# gateDriverProto.net
KiCad netlist of a schematic drawn in EAGLE
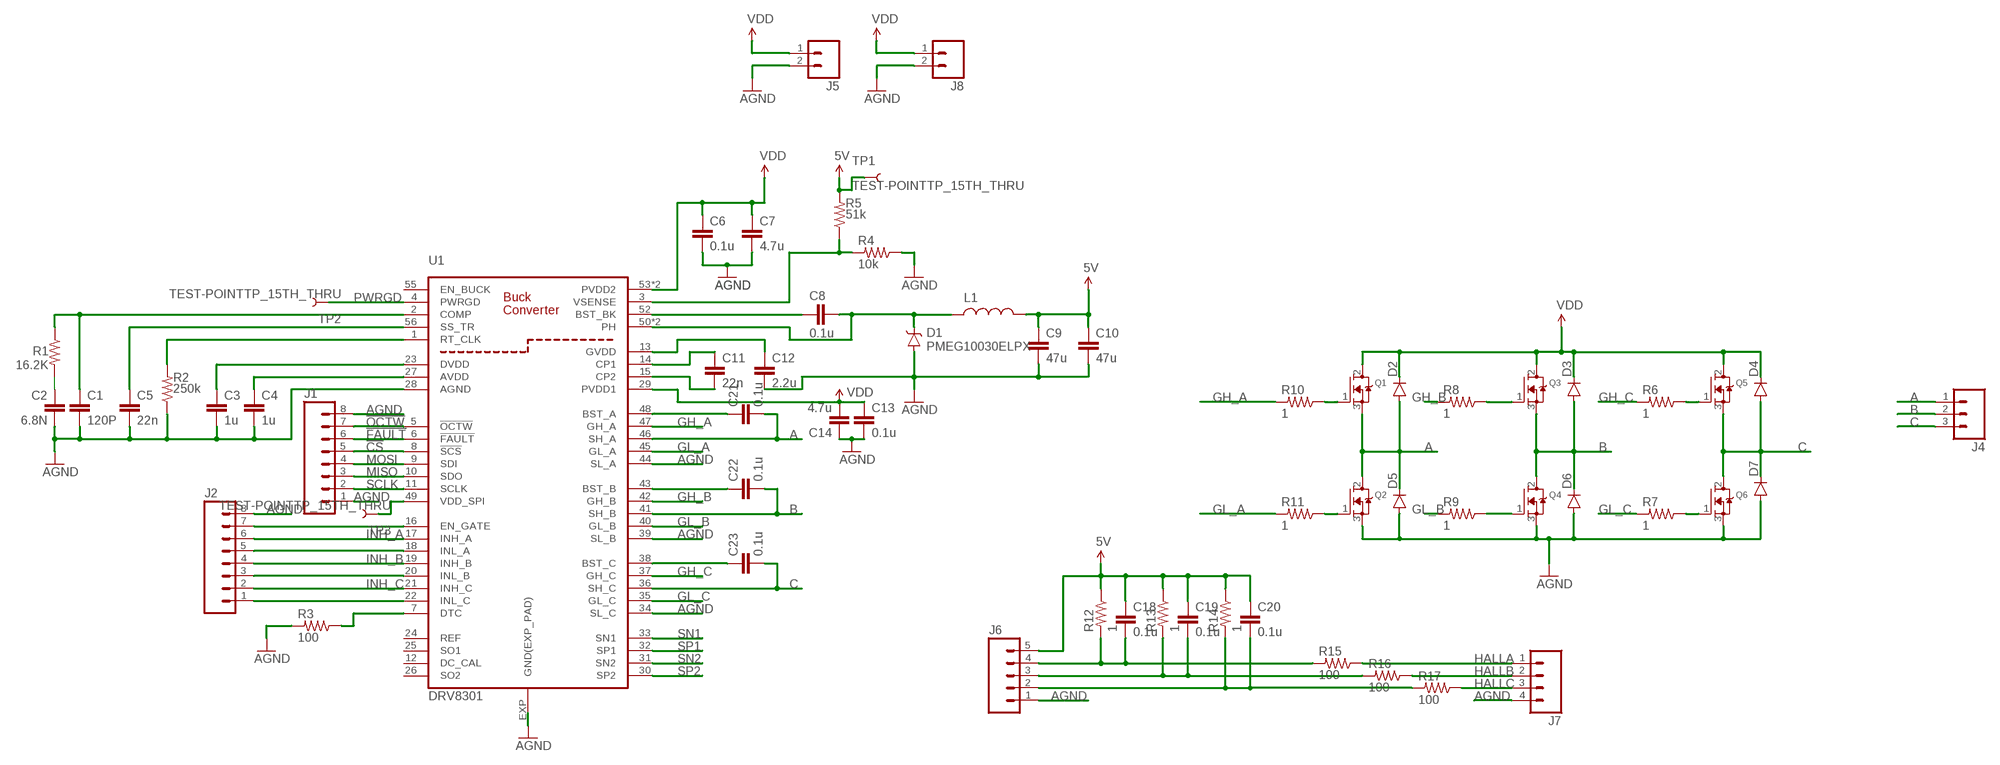
[diagram p0: schematic, sheet 1]

(export (version "E")
  (design (tool "Eeschema 10.0.6"))
  (components
    (comp (ref "C1")
      (value "120P")
      (footprint "eagle-import:0805")
      (libsource (lib "eagle-import") (part "CAP0805"))
    )
    (comp (ref "C2")
      (value "6.8N")
      (footprint "eagle-import:0805")
      (libsource (lib "eagle-import") (part "CAP0805"))
    )
    (comp (ref "C3")
      (value "1u")
      (footprint "eagle-import:0805")
      (libsource (lib "eagle-import") (part "CAP0805"))
    )
    (comp (ref "C4")
      (value "1u")
      (footprint "eagle-import:0805")
      (libsource (lib "eagle-import") (part "CAP0805"))
    )
    (comp (ref "C5")
      (value "22n")
      (footprint "eagle-import:0805")
      (libsource (lib "eagle-import") (part "CAP0805"))
    )
    (comp (ref "C6")
      (value "0.1u")
      (footprint "eagle-import:0805")
      (libsource (lib "eagle-import") (part "CAP0805"))
    )
    (comp (ref "C7")
      (value "4.7u")
      (footprint "eagle-import:1210")
      (libsource (lib "eagle-import") (part "CAP1210"))
    )
    (comp (ref "C8")
      (value "0.1u")
      (footprint "eagle-import:0805")
      (libsource (lib "eagle-import") (part "CAP0805"))
    )
    (comp (ref "C9")
      (value "47u")
      (footprint "eagle-import:1210")
      (libsource (lib "eagle-import") (part "CAP1210"))
    )
    (comp (ref "C10")
      (value "47u")
      (footprint "eagle-import:1210")
      (libsource (lib "eagle-import") (part "CAP1210"))
    )
    (comp (ref "C11")
      (value "22n")
      (footprint "eagle-import:0805")
      (libsource (lib "eagle-import") (part "CAP0805"))
    )
    (comp (ref "C12")
      (value "2.2u")
      (footprint "eagle-import:1210")
      (libsource (lib "eagle-import") (part "CAP1210"))
    )
    (comp (ref "C13")
      (value "0.1u")
      (footprint "eagle-import:0805")
      (libsource (lib "eagle-import") (part "CAP0805"))
    )
    (comp (ref "C14")
      (value "4.7u")
      (footprint "eagle-import:1210")
      (libsource (lib "eagle-import") (part "CAP1210"))
    )
    (comp (ref "C18")
      (value "0.1u")
      (footprint "eagle-import:0805")
      (libsource (lib "eagle-import") (part "CAP0805"))
    )
    (comp (ref "C19")
      (value "0.1u")
      (footprint "eagle-import:0805")
      (libsource (lib "eagle-import") (part "CAP0805"))
    )
    (comp (ref "C20")
      (value "0.1u")
      (footprint "eagle-import:0805")
      (libsource (lib "eagle-import") (part "CAP0805"))
    )
    (comp (ref "C21")
      (value "0.1u")
      (footprint "eagle-import:CAP-PTH-SMALL")
      (libsource (lib "eagle-import") (part "SparkFun-Passives_CAPPTH"))
    )
    (comp (ref "C22")
      (value "0.1u")
      (footprint "eagle-import:CAP-PTH-SMALL")
      (libsource (lib "eagle-import") (part "SparkFun-Passives_CAPPTH"))
    )
    (comp (ref "C23")
      (value "0.1u")
      (footprint "eagle-import:CAP-PTH-SMALL")
      (libsource (lib "eagle-import") (part "SparkFun-Passives_CAPPTH"))
    )
    (comp (ref "D1")
      (value "PMEG10030ELPX")
      (footprint "eagle-import:SMB-DIODE")
      (libsource (lib "eagle-import") (part "PMEG10030ELPX"))
    )
    (comp (ref "D2")
      (value "DIODEPTH")
      (footprint "eagle-import:DIODE-1N4001")
      (libsource (lib "eagle-import") (part "DIODEPTH"))
    )
    (comp (ref "D3")
      (value "DIODEPTH")
      (footprint "eagle-import:DIODE-1N4001")
      (libsource (lib "eagle-import") (part "DIODEPTH"))
    )
    (comp (ref "D4")
      (value "DIODEPTH")
      (footprint "eagle-import:DIODE-1N4001")
      (libsource (lib "eagle-import") (part "DIODEPTH"))
    )
    (comp (ref "D5")
      (value "DIODEPTH")
      (footprint "eagle-import:DIODE-1N4001")
      (libsource (lib "eagle-import") (part "DIODEPTH"))
    )
    (comp (ref "D6")
      (value "DIODEPTH")
      (footprint "eagle-import:DIODE-1N4001")
      (libsource (lib "eagle-import") (part "DIODEPTH"))
    )
    (comp (ref "D7")
      (value "DIODEPTH")
      (footprint "eagle-import:DIODE-1N4001")
      (libsource (lib "eagle-import") (part "DIODEPTH"))
    )
    (comp (ref "J1")
      (value "M08")
      (footprint "eagle-import:1X08_ROUND")
      (libsource (lib "eagle-import") (part "M08"))
    )
    (comp (ref "J2")
      (value "M08")
      (footprint "eagle-import:1X08_ROUND")
      (libsource (lib "eagle-import") (part "M08"))
    )
    (comp (ref "J4")
      (value "M03LONGPADS")
      (footprint "eagle-import:1X03_LONGPADS")
      (libsource (lib "eagle-import") (part "M03LONGPADS"))
    )
    (comp (ref "J5")
      (value "M02LOCK_LONGPADS")
      (footprint "eagle-import:1X02_LOCK_LONGPADS")
      (libsource (lib "eagle-import") (part "M02LOCK_LONGPADS"))
    )
    (comp (ref "J6")
      (value "M05PTH_LONGPADS")
      (footprint "eagle-import:1X05_LONGPADS")
      (libsource (lib "eagle-import") (part "M05PTH_LONGPADS"))
    )
    (comp (ref "J7")
      (value "M04PTH")
      (footprint "eagle-import:1X04")
      (libsource (lib "eagle-import") (part "M04PTH"))
    )
    (comp (ref "J8")
      (value "M02LOCK_LONGPADS")
      (footprint "eagle-import:1X02_LOCK_LONGPADS")
      (libsource (lib "eagle-import") (part "M02LOCK_LONGPADS"))
    )
    (comp (ref "L1")
      (value "INDUCTORPWR")
      (footprint "eagle-import:CDRH125")
      (libsource (lib "eagle-import") (part "INDUCTORPWR"))
    )
    (comp (ref "Q1")
      (value "MOSFET-NGDS_TO220V")
      (footprint "eagle-import:TO220V")
      (libsource (lib "eagle-import") (part "MOSFET-NGDS_TO220V"))
    )
    (comp (ref "Q2")
      (value "MOSFET-NGDS_TO220V")
      (footprint "eagle-import:TO220V")
      (libsource (lib "eagle-import") (part "MOSFET-NGDS_TO220V"))
    )
    (comp (ref "Q3")
      (value "MOSFET-NGDS_TO220V")
      (footprint "eagle-import:TO220V")
      (libsource (lib "eagle-import") (part "MOSFET-NGDS_TO220V"))
    )
    (comp (ref "Q4")
      (value "MOSFET-NGDS_TO220V")
      (footprint "eagle-import:TO220V")
      (libsource (lib "eagle-import") (part "MOSFET-NGDS_TO220V"))
    )
    (comp (ref "Q5")
      (value "MOSFET-NGDS_TO220V")
      (footprint "eagle-import:TO220V")
      (libsource (lib "eagle-import") (part "MOSFET-NGDS_TO220V"))
    )
    (comp (ref "Q6")
      (value "MOSFET-NGDS_TO220V")
      (footprint "eagle-import:TO220V")
      (libsource (lib "eagle-import") (part "MOSFET-NGDS_TO220V"))
    )
    (comp (ref "R1")
      (value "16.2K")
      (footprint "eagle-import:AXIAL-0.1")
      (libsource (lib "eagle-import") (part "RESISTORPTH-1/4W-VERT"))
    )
    (comp (ref "R2")
      (value "250k")
      (footprint "eagle-import:AXIAL-0.1")
      (libsource (lib "eagle-import") (part "RESISTORPTH-1/4W-VERT"))
    )
    (comp (ref "R3")
      (value "100")
      (footprint "eagle-import:AXIAL-0.1")
      (libsource (lib "eagle-import") (part "RESISTORPTH-1/4W-VERT"))
    )
    (comp (ref "R4")
      (value "10k")
      (footprint "eagle-import:AXIAL-0.1")
      (libsource (lib "eagle-import") (part "RESISTORPTH-1/4W-VERT"))
    )
    (comp (ref "R5")
      (value "51k")
      (footprint "eagle-import:AXIAL-0.1")
      (libsource (lib "eagle-import") (part "RESISTORPTH-1/4W-VERT"))
    )
    (comp (ref "R6")
      (value "1")
      (footprint "eagle-import:AXIAL-0.1")
      (libsource (lib "eagle-import") (part "RESISTORPTH-1/4W-VERT"))
    )
    (comp (ref "R7")
      (value "1")
      (footprint "eagle-import:AXIAL-0.1")
      (libsource (lib "eagle-import") (part "RESISTORPTH-1/4W-VERT"))
    )
    (comp (ref "R8")
      (value "1")
      (footprint "eagle-import:AXIAL-0.1")
      (libsource (lib "eagle-import") (part "RESISTORPTH-1/4W-VERT"))
    )
    (comp (ref "R9")
      (value "1")
      (footprint "eagle-import:AXIAL-0.1")
      (libsource (lib "eagle-import") (part "RESISTORPTH-1/4W-VERT"))
    )
    (comp (ref "R10")
      (value "1")
      (footprint "eagle-import:AXIAL-0.1")
      (libsource (lib "eagle-import") (part "RESISTORPTH-1/4W-VERT"))
    )
    (comp (ref "R11")
      (value "1")
      (footprint "eagle-import:AXIAL-0.1")
      (libsource (lib "eagle-import") (part "RESISTORPTH-1/4W-VERT"))
    )
    (comp (ref "R12")
      (value "1")
      (footprint "eagle-import:AXIAL-0.1")
      (libsource (lib "eagle-import") (part "RESISTORPTH-1/4W-VERT"))
    )
    (comp (ref "R13")
      (value "1")
      (footprint "eagle-import:AXIAL-0.1")
      (libsource (lib "eagle-import") (part "RESISTORPTH-1/4W-VERT"))
    )
    (comp (ref "R14")
      (value "1")
      (footprint "eagle-import:AXIAL-0.1")
      (libsource (lib "eagle-import") (part "RESISTORPTH-1/4W-VERT"))
    )
    (comp (ref "R15")
      (value "100")
      (footprint "eagle-import:AXIAL-0.1")
      (libsource (lib "eagle-import") (part "RESISTORPTH-1/4W-VERT"))
    )
    (comp (ref "R16")
      (value "100")
      (footprint "eagle-import:AXIAL-0.1")
      (libsource (lib "eagle-import") (part "RESISTORPTH-1/4W-VERT"))
    )
    (comp (ref "R17")
      (value "100")
      (footprint "eagle-import:AXIAL-0.1")
      (libsource (lib "eagle-import") (part "RESISTORPTH-1/4W-VERT"))
    )
    (comp (ref "TP1")
      (value "TEST-POINTTP_15TH_THRU")
      (footprint "eagle-import:TP_15TH")
      (libsource (lib "eagle-import") (part "TEST-POINTTP_15TH_THRU"))
    )
    (comp (ref "TP2")
      (value "TEST-POINTTP_15TH_THRU")
      (footprint "eagle-import:TP_15TH")
      (libsource (lib "eagle-import") (part "TEST-POINTTP_15TH_THRU"))
    )
    (comp (ref "TP3")
      (value "TEST-POINTTP_15TH_THRU")
      (footprint "eagle-import:TP_15TH")
      (libsource (lib "eagle-import") (part "TEST-POINTTP_15TH_THRU"))
    )
    (comp (ref "U1")
      (value "DRV8301")
      (footprint "eagle-import:HTSSOP_56")
      (libsource (lib "eagle-import") (part "DRV8301"))
    )
  )
  (nets
    (net (code "1") (name "/A") (class "Default")
      (node (ref "C21") (pin "2") (pinfunction "2_2") (pintype "passive"))
      (node (ref "D2") (pin "A") (pinfunction "A_A") (pintype "passive"))
      (node (ref "D5") (pin "C") (pinfunction "C_C") (pintype "passive"))
      (node (ref "J4") (pin "1") (pinfunction "1_1") (pintype "passive"))
      (node (ref "Q1") (pin "3") (pinfunction "S_3") (pintype "bidirectional"))
      (node (ref "Q2") (pin "2") (pinfunction "D_2") (pintype "bidirectional"))
      (node (ref "U1") (pin "46") (pinfunction "SH_A_46") (pintype "input"))
    )
    (net (code "2") (name "/B") (class "Default")
      (node (ref "C22") (pin "2") (pinfunction "2_2") (pintype "passive"))
      (node (ref "D3") (pin "A") (pinfunction "A_A") (pintype "passive"))
      (node (ref "D6") (pin "C") (pinfunction "C_C") (pintype "passive"))
      (node (ref "J4") (pin "2") (pinfunction "2_2") (pintype "passive"))
      (node (ref "Q3") (pin "3") (pinfunction "S_3") (pintype "bidirectional"))
      (node (ref "Q4") (pin "2") (pinfunction "D_2") (pintype "bidirectional"))
      (node (ref "U1") (pin "41") (pinfunction "SH_B_41") (pintype "input"))
    )
    (net (code "3") (name "/C") (class "Default")
      (node (ref "C23") (pin "2") (pinfunction "2_2") (pintype "passive"))
      (node (ref "D4") (pin "A") (pinfunction "A_A") (pintype "passive"))
      (node (ref "D7") (pin "C") (pinfunction "C_C") (pintype "passive"))
      (node (ref "J4") (pin "3") (pinfunction "3_3") (pintype "passive"))
      (node (ref "Q5") (pin "3") (pinfunction "S_3") (pintype "bidirectional"))
      (node (ref "Q6") (pin "2") (pinfunction "D_2") (pintype "bidirectional"))
      (node (ref "U1") (pin "36") (pinfunction "SH_C_36") (pintype "input"))
    )
    (net (code "4") (name "/GH_A") (class "Default")
      (node (ref "R10") (pin "P$2") (pinfunction "2_P$2") (pintype "passive"))
      (node (ref "U1") (pin "47") (pinfunction "GH_A_47") (pintype "output"))
    )
    (net (code "5") (name "/GH_B") (class "Default")
      (node (ref "R8") (pin "P$2") (pinfunction "2_P$2") (pintype "passive"))
      (node (ref "U1") (pin "42") (pinfunction "GH_B_42") (pintype "output"))
    )
    (net (code "6") (name "/GH_C") (class "Default")
      (node (ref "R6") (pin "P$2") (pinfunction "2_P$2") (pintype "passive"))
      (node (ref "U1") (pin "37") (pinfunction "GH_C_37") (pintype "output"))
    )
    (net (code "7") (name "/GL_A") (class "Default")
      (node (ref "R11") (pin "P$2") (pinfunction "2_P$2") (pintype "passive"))
      (node (ref "U1") (pin "45") (pinfunction "GL_A_45") (pintype "output"))
    )
    (net (code "8") (name "/GL_B") (class "Default")
      (node (ref "R9") (pin "P$2") (pinfunction "2_P$2") (pintype "passive"))
      (node (ref "U1") (pin "40") (pinfunction "GL_B_40") (pintype "output"))
    )
    (net (code "9") (name "/GL_C") (class "Default")
      (node (ref "R7") (pin "P$2") (pinfunction "2_P$2") (pintype "passive"))
      (node (ref "U1") (pin "35") (pinfunction "GL_C_35") (pintype "output"))
    )
    (net (code "10") (name "/HALLA") (class "Default")
      (node (ref "J7") (pin "1") (pinfunction "1_1") (pintype "passive"))
      (node (ref "R15") (pin "P$1") (pinfunction "1_P$1") (pintype "passive"))
    )
    (net (code "11") (name "/HALLB") (class "Default")
      (node (ref "J7") (pin "2") (pinfunction "2_2") (pintype "passive"))
      (node (ref "R16") (pin "P$1") (pinfunction "1_P$1") (pintype "passive"))
    )
    (net (code "12") (name "/HALLC") (class "Default")
      (node (ref "J7") (pin "3") (pinfunction "3_3") (pintype "passive"))
      (node (ref "R17") (pin "P$1") (pinfunction "1_P$1") (pintype "passive"))
    )
    (net (code "13") (name "/INH_A") (class "Default")
      (node (ref "J2") (pin "6") (pinfunction "6_6") (pintype "passive"))
      (node (ref "U1") (pin "17") (pinfunction "INH_A_17") (pintype "input"))
    )
    (net (code "14") (name "/INH_B") (class "Default")
      (node (ref "J2") (pin "4") (pinfunction "4_4") (pintype "passive"))
      (node (ref "U1") (pin "19") (pinfunction "INH_B_19") (pintype "input"))
    )
    (net (code "15") (name "/INH_C") (class "Default")
      (node (ref "J2") (pin "2") (pinfunction "2_2") (pintype "passive"))
      (node (ref "U1") (pin "21") (pinfunction "INH_C_21") (pintype "input"))
    )
    (net (code "16") (name "/MISO") (class "Default")
      (node (ref "J1") (pin "3") (pinfunction "3_3") (pintype "passive"))
      (node (ref "U1") (pin "10") (pinfunction "SDO_10") (pintype "output"))
    )
    (net (code "17") (name "/MOSI") (class "Default")
      (node (ref "J1") (pin "4") (pinfunction "4_4") (pintype "passive"))
      (node (ref "U1") (pin "9") (pinfunction "SDI_9") (pintype "input"))
    )
    (net (code "18") (name "/PWRGD") (class "Default")
      (node (ref "TP2") (pin "P$1") (pinfunction "1_P$1") (pintype "bidirectional"))
      (node (ref "U1") (pin "4") (pinfunction "PWRGD_4") (pintype "output"))
    )
    (net (code "19") (name "/SCLK") (class "Default")
      (node (ref "J1") (pin "2") (pinfunction "2_2") (pintype "passive"))
      (node (ref "U1") (pin "11") (pinfunction "SCLK_11") (pintype "input"))
    )
    (net (code "20") (name "/SN1") (class "Default")
      (node (ref "U1") (pin "33") (pinfunction "SN1_33") (pintype "input"))
    )
    (net (code "21") (name "/SN2") (class "Default")
      (node (ref "U1") (pin "31") (pinfunction "SN2_31") (pintype "input"))
    )
    (net (code "22") (name "/SP1") (class "Default")
      (node (ref "U1") (pin "32") (pinfunction "SP1_32") (pintype "input"))
    )
    (net (code "23") (name "/SP2") (class "Default")
      (node (ref "U1") (pin "30") (pinfunction "SP2_30") (pintype "input"))
    )
    (net (code "24") (name "/~{CS}") (class "Default")
      (node (ref "J1") (pin "5") (pinfunction "5_5") (pintype "passive"))
      (node (ref "U1") (pin "8") (pinfunction "~{SCS}_8") (pintype "input"))
    )
    (net (code "25") (name "/~{FAULT}") (class "Default")
      (node (ref "J1") (pin "6") (pinfunction "6_6") (pintype "passive"))
      (node (ref "U1") (pin "6") (pinfunction "~{FAULT}_6") (pintype "output"))
    )
    (net (code "26") (name "/~{OCTW}") (class "Default")
      (node (ref "J1") (pin "7") (pinfunction "7_7") (pintype "passive"))
      (node (ref "U1") (pin "5") (pinfunction "~{OCTW}_5") (pintype "output"))
    )
    (net (code "27") (name "5V") (class "Default")
      (node (ref "C10") (pin "1") (pinfunction "1_1") (pintype "passive"))
      (node (ref "C18") (pin "1") (pinfunction "1_1") (pintype "passive"))
      (node (ref "C19") (pin "1") (pinfunction "1_1") (pintype "passive"))
      (node (ref "C20") (pin "1") (pinfunction "1_1") (pintype "passive"))
      (node (ref "C9") (pin "1") (pinfunction "1_1") (pintype "passive"))
      (node (ref "J6") (pin "5") (pinfunction "5_5") (pintype "passive"))
      (node (ref "L1") (pin "2") (pinfunction "2_2") (pintype "passive"))
      (node (ref "R12") (pin "P$1") (pinfunction "1_P$1") (pintype "passive"))
      (node (ref "R13") (pin "P$1") (pinfunction "1_P$1") (pintype "passive"))
      (node (ref "R14") (pin "P$1") (pinfunction "1_P$1") (pintype "passive"))
      (node (ref "R5") (pin "P$2") (pinfunction "2_P$2") (pintype "passive"))
      (node (ref "TP1") (pin "P$1") (pinfunction "1_P$1") (pintype "bidirectional"))
    )
    (net (code "28") (name "AGND") (class "Default")
      (node (ref "C1") (pin "2") (pinfunction "2_2") (pintype "passive"))
      (node (ref "C10") (pin "2") (pinfunction "2_2") (pintype "passive"))
      (node (ref "C12") (pin "2") (pinfunction "2_2") (pintype "passive"))
      (node (ref "C13") (pin "2") (pinfunction "2_2") (pintype "passive"))
      (node (ref "C14") (pin "1") (pinfunction "1_1") (pintype "passive"))
      (node (ref "C2") (pin "2") (pinfunction "2_2") (pintype "passive"))
      (node (ref "C3") (pin "2") (pinfunction "2_2") (pintype "passive"))
      (node (ref "C4") (pin "2") (pinfunction "2_2") (pintype "passive"))
      (node (ref "C5") (pin "2") (pinfunction "2_2") (pintype "passive"))
      (node (ref "C6") (pin "2") (pinfunction "2_2") (pintype "passive"))
      (node (ref "C7") (pin "2") (pinfunction "2_2") (pintype "passive"))
      (node (ref "C9") (pin "2") (pinfunction "2_2") (pintype "passive"))
      (node (ref "D1") (pin "A") (pinfunction "A_A") (pintype "passive"))
      (node (ref "D5") (pin "A") (pinfunction "A_A") (pintype "passive"))
      (node (ref "D6") (pin "A") (pinfunction "A_A") (pintype "passive"))
      (node (ref "D7") (pin "A") (pinfunction "A_A") (pintype "passive"))
      (node (ref "J1") (pin "1") (pinfunction "1_1") (pintype "passive"))
      (node (ref "J1") (pin "8") (pinfunction "8_8") (pintype "passive"))
      (node (ref "J2") (pin "8") (pinfunction "8_8") (pintype "passive"))
      (node (ref "J5") (pin "2") (pinfunction "2_2") (pintype "passive"))
      (node (ref "J6") (pin "1") (pinfunction "1_1") (pintype "passive"))
      (node (ref "J7") (pin "4") (pinfunction "4_4") (pintype "passive"))
      (node (ref "J8") (pin "2") (pinfunction "2_2") (pintype "passive"))
      (node (ref "Q2") (pin "3") (pinfunction "S_3") (pintype "bidirectional"))
      (node (ref "Q4") (pin "3") (pinfunction "S_3") (pintype "bidirectional"))
      (node (ref "Q6") (pin "3") (pinfunction "S_3") (pintype "bidirectional"))
      (node (ref "R2") (pin "P$1") (pinfunction "1_P$1") (pintype "passive"))
      (node (ref "R3") (pin "P$2") (pinfunction "2_P$2") (pintype "passive"))
      (node (ref "R4") (pin "P$1") (pinfunction "1_P$1") (pintype "passive"))
      (node (ref "U1") (pin "28") (pinfunction "AGND_28") (pintype "power_in"))
      (node (ref "U1") (pin "34") (pinfunction "SL_C_34") (pintype "input"))
      (node (ref "U1") (pin "39") (pinfunction "SL_B_39") (pintype "input"))
      (node (ref "U1") (pin "44") (pinfunction "SL_A_44") (pintype "input"))
      (node (ref "U1") (pin "EXP") (pinfunction "GND(EXP_PAD)_EXP") (pintype "bidirectional"))
    )
    (net (code "29") (name "Net-(C8-Pad2)") (class "Default")
      (node (ref "C8") (pin "2") (pinfunction "2_2") (pintype "passive"))
      (node (ref "D1") (pin "C") (pinfunction "C_C") (pintype "passive"))
      (node (ref "L1") (pin "1") (pinfunction "1_1") (pintype "passive"))
      (node (ref "U1") (pin "50") (pinfunction "PH_50") (pintype "output"))
      (node (ref "U1") (pin "51") (pinfunction "PH_51") (pintype "output"))
    )
    (net (code "30") (name "Net-(Q1-G)") (class "Default")
      (node (ref "Q1") (pin "1") (pinfunction "G_1") (pintype "bidirectional"))
      (node (ref "R10") (pin "P$1") (pinfunction "1_P$1") (pintype "passive"))
    )
    (net (code "31") (name "Net-(Q2-G)") (class "Default")
      (node (ref "Q2") (pin "1") (pinfunction "G_1") (pintype "bidirectional"))
      (node (ref "R11") (pin "P$1") (pinfunction "1_P$1") (pintype "passive"))
    )
    (net (code "32") (name "Net-(Q3-G)") (class "Default")
      (node (ref "Q3") (pin "1") (pinfunction "G_1") (pintype "bidirectional"))
      (node (ref "R8") (pin "P$1") (pinfunction "1_P$1") (pintype "passive"))
    )
    (net (code "33") (name "Net-(Q4-G)") (class "Default")
      (node (ref "Q4") (pin "1") (pinfunction "G_1") (pintype "bidirectional"))
      (node (ref "R9") (pin "P$1") (pinfunction "1_P$1") (pintype "passive"))
    )
    (net (code "34") (name "Net-(Q5-G)") (class "Default")
      (node (ref "Q5") (pin "1") (pinfunction "G_1") (pintype "bidirectional"))
      (node (ref "R6") (pin "P$1") (pinfunction "1_P$1") (pintype "passive"))
    )
    (net (code "35") (name "Net-(Q6-G)") (class "Default")
      (node (ref "Q6") (pin "1") (pinfunction "G_1") (pintype "bidirectional"))
      (node (ref "R7") (pin "P$1") (pinfunction "1_P$1") (pintype "passive"))
    )
    (net (code "36") (name "Net-(R1-1)") (class "Default")
      (node (ref "C1") (pin "1") (pinfunction "1_1") (pintype "passive"))
      (node (ref "R1") (pin "P$1") (pinfunction "1_P$1") (pintype "passive"))
      (node (ref "U1") (pin "2") (pinfunction "COMP_2") (pintype "output"))
    )
    (net (code "37") (name "Net-(R1-2)") (class "Default")
      (node (ref "C2") (pin "1") (pinfunction "1_1") (pintype "passive"))
      (node (ref "R1") (pin "P$2") (pinfunction "2_P$2") (pintype "passive"))
    )
    (net (code "38") (name "Net-(R2-2)") (class "Default")
      (node (ref "R2") (pin "P$2") (pinfunction "2_P$2") (pintype "passive"))
      (node (ref "U1") (pin "1") (pinfunction "RT_CLK_1") (pintype "input"))
    )
    (net (code "39") (name "Net-(R3-1)") (class "Default")
      (node (ref "R3") (pin "P$1") (pinfunction "1_P$1") (pintype "passive"))
      (node (ref "U1") (pin "7") (pinfunction "DTC_7") (pintype "input"))
    )
    (net (code "40") (name "Net-(R4-2)") (class "Default")
      (node (ref "R4") (pin "P$2") (pinfunction "2_P$2") (pintype "passive"))
      (node (ref "R5") (pin "P$1") (pinfunction "1_P$1") (pintype "passive"))
      (node (ref "U1") (pin "3") (pinfunction "VSENSE_3") (pintype "input"))
    )
    (net (code "41") (name "Net-(R12-2)") (class "Default")
      (node (ref "C18") (pin "2") (pinfunction "2_2") (pintype "passive"))
      (node (ref "J6") (pin "4") (pinfunction "4_4") (pintype "passive"))
      (node (ref "R12") (pin "P$2") (pinfunction "2_P$2") (pintype "passive"))
      (node (ref "R15") (pin "P$2") (pinfunction "2_P$2") (pintype "passive"))
    )
    (net (code "42") (name "Net-(R13-2)") (class "Default")
      (node (ref "C19") (pin "2") (pinfunction "2_2") (pintype "passive"))
      (node (ref "J6") (pin "3") (pinfunction "3_3") (pintype "passive"))
      (node (ref "R13") (pin "P$2") (pinfunction "2_P$2") (pintype "passive"))
      (node (ref "R16") (pin "P$2") (pinfunction "2_P$2") (pintype "passive"))
    )
    (net (code "43") (name "Net-(R14-2)") (class "Default")
      (node (ref "C20") (pin "2") (pinfunction "2_2") (pintype "passive"))
      (node (ref "J6") (pin "2") (pinfunction "2_2") (pintype "passive"))
      (node (ref "R14") (pin "P$2") (pinfunction "2_P$2") (pintype "passive"))
      (node (ref "R17") (pin "P$2") (pinfunction "2_P$2") (pintype "passive"))
    )
    (net (code "44") (name "Net-(TP3-1)") (class "Default")
      (node (ref "TP3") (pin "P$1") (pinfunction "1_P$1") (pintype "bidirectional"))
      (node (ref "U1") (pin "49") (pinfunction "VDD_SPI_49") (pintype "input"))
    )
    (net (code "45") (name "Net-(U1-AVDD)") (class "Default")
      (node (ref "C4") (pin "1") (pinfunction "1_1") (pintype "passive"))
      (node (ref "U1") (pin "27") (pinfunction "AVDD_27") (pintype "power_in"))
    )
    (net (code "46") (name "Net-(U1-BST_A)") (class "Default")
      (node (ref "C21") (pin "1") (pinfunction "1_1") (pintype "passive"))
      (node (ref "U1") (pin "48") (pinfunction "BST_A_48") (pintype "power_in"))
    )
    (net (code "47") (name "Net-(U1-BST_B)") (class "Default")
      (node (ref "C22") (pin "1") (pinfunction "1_1") (pintype "passive"))
      (node (ref "U1") (pin "43") (pinfunction "BST_B_43") (pintype "power_in"))
    )
    (net (code "48") (name "Net-(U1-BST_BK)") (class "Default")
      (node (ref "C8") (pin "1") (pinfunction "1_1") (pintype "passive"))
      (node (ref "U1") (pin "52") (pinfunction "BST_BK_52") (pintype "power_in"))
    )
    (net (code "49") (name "Net-(U1-BST_C)") (class "Default")
      (node (ref "C23") (pin "1") (pinfunction "1_1") (pintype "passive"))
      (node (ref "U1") (pin "38") (pinfunction "BST_C_38") (pintype "power_in"))
    )
    (net (code "50") (name "Net-(U1-CP1)") (class "Default")
      (node (ref "C11") (pin "1") (pinfunction "1_1") (pintype "passive"))
      (node (ref "U1") (pin "14") (pinfunction "CP1_14") (pintype "power_in"))
    )
    (net (code "51") (name "Net-(U1-CP2)") (class "Default")
      (node (ref "C11") (pin "2") (pinfunction "2_2") (pintype "passive"))
      (node (ref "U1") (pin "15") (pinfunction "CP2_15") (pintype "power_in"))
    )
    (net (code "52") (name "Net-(U1-DVDD)") (class "Default")
      (node (ref "C3") (pin "1") (pinfunction "1_1") (pintype "passive"))
      (node (ref "U1") (pin "23") (pinfunction "DVDD_23") (pintype "power_in"))
    )
    (net (code "53") (name "Net-(U1-EN_GATE)") (class "Default")
      (node (ref "J2") (pin "7") (pinfunction "7_7") (pintype "passive"))
      (node (ref "U1") (pin "16") (pinfunction "EN_GATE_16") (pintype "input"))
    )
    (net (code "54") (name "Net-(U1-GVDD)") (class "Default")
      (node (ref "C12") (pin "1") (pinfunction "1_1") (pintype "passive"))
      (node (ref "U1") (pin "13") (pinfunction "GVDD_13") (pintype "power_in"))
    )
    (net (code "55") (name "Net-(U1-INL_A)") (class "Default")
      (node (ref "J2") (pin "5") (pinfunction "5_5") (pintype "passive"))
      (node (ref "U1") (pin "18") (pinfunction "INL_A_18") (pintype "input"))
    )
    (net (code "56") (name "Net-(U1-INL_B)") (class "Default")
      (node (ref "J2") (pin "3") (pinfunction "3_3") (pintype "passive"))
      (node (ref "U1") (pin "20") (pinfunction "INL_B_20") (pintype "input"))
    )
    (net (code "57") (name "Net-(U1-INL_C)") (class "Default")
      (node (ref "J2") (pin "1") (pinfunction "1_1") (pintype "passive"))
      (node (ref "U1") (pin "22") (pinfunction "INL_C_22") (pintype "input"))
    )
    (net (code "58") (name "Net-(U1-SS_TR)") (class "Default")
      (node (ref "C5") (pin "1") (pinfunction "1_1") (pintype "passive"))
      (node (ref "U1") (pin "56") (pinfunction "SS_TR_56") (pintype "input"))
    )
    (net (code "59") (name "VDD") (class "Default")
      (node (ref "C13") (pin "1") (pinfunction "1_1") (pintype "passive"))
      (node (ref "C14") (pin "2") (pinfunction "2_2") (pintype "passive"))
      (node (ref "C6") (pin "1") (pinfunction "1_1") (pintype "passive"))
      (node (ref "C7") (pin "1") (pinfunction "1_1") (pintype "passive"))
      (node (ref "D2") (pin "C") (pinfunction "C_C") (pintype "passive"))
      (node (ref "D3") (pin "C") (pinfunction "C_C") (pintype "passive"))
      (node (ref "D4") (pin "C") (pinfunction "C_C") (pintype "passive"))
      (node (ref "J5") (pin "1") (pinfunction "1_1") (pintype "passive"))
      (node (ref "J8") (pin "1") (pinfunction "1_1") (pintype "passive"))
      (node (ref "Q1") (pin "2") (pinfunction "D_2") (pintype "bidirectional"))
      (node (ref "Q3") (pin "2") (pinfunction "D_2") (pintype "bidirectional"))
      (node (ref "Q5") (pin "2") (pinfunction "D_2") (pintype "bidirectional"))
      (node (ref "U1") (pin "29") (pinfunction "PVDD1_29") (pintype "power_in"))
      (node (ref "U1") (pin "53") (pinfunction "PVDD2_53") (pintype "power_in"))
      (node (ref "U1") (pin "54") (pinfunction "PVDD2_54") (pintype "power_in"))
    )
    (net (code "60") (name "unconnected-(U1-DC_CAL-Pad12)") (class "Default")
      (node (ref "U1") (pin "12") (pinfunction "DC_CAL_12") (pintype "input"))
    )
    (net (code "61") (name "unconnected-(U1-EN_BUCK-Pad55)") (class "Default")
      (node (ref "U1") (pin "55") (pinfunction "EN_BUCK_55") (pintype "input"))
    )
    (net (code "62") (name "unconnected-(U1-REF-Pad24)") (class "Default")
      (node (ref "U1") (pin "24") (pinfunction "REF_24") (pintype "input"))
    )
    (net (code "63") (name "unconnected-(U1-SO1-Pad25)") (class "Default")
      (node (ref "U1") (pin "25") (pinfunction "SO1_25") (pintype "output"))
    )
    (net (code "64") (name "unconnected-(U1-SO2-Pad26)") (class "Default")
      (node (ref "U1") (pin "26") (pinfunction "SO2_26") (pintype "output"))
    )
  )
)
